# circuitdraft.net
KiCad netlist of a schematic drawn in EAGLE
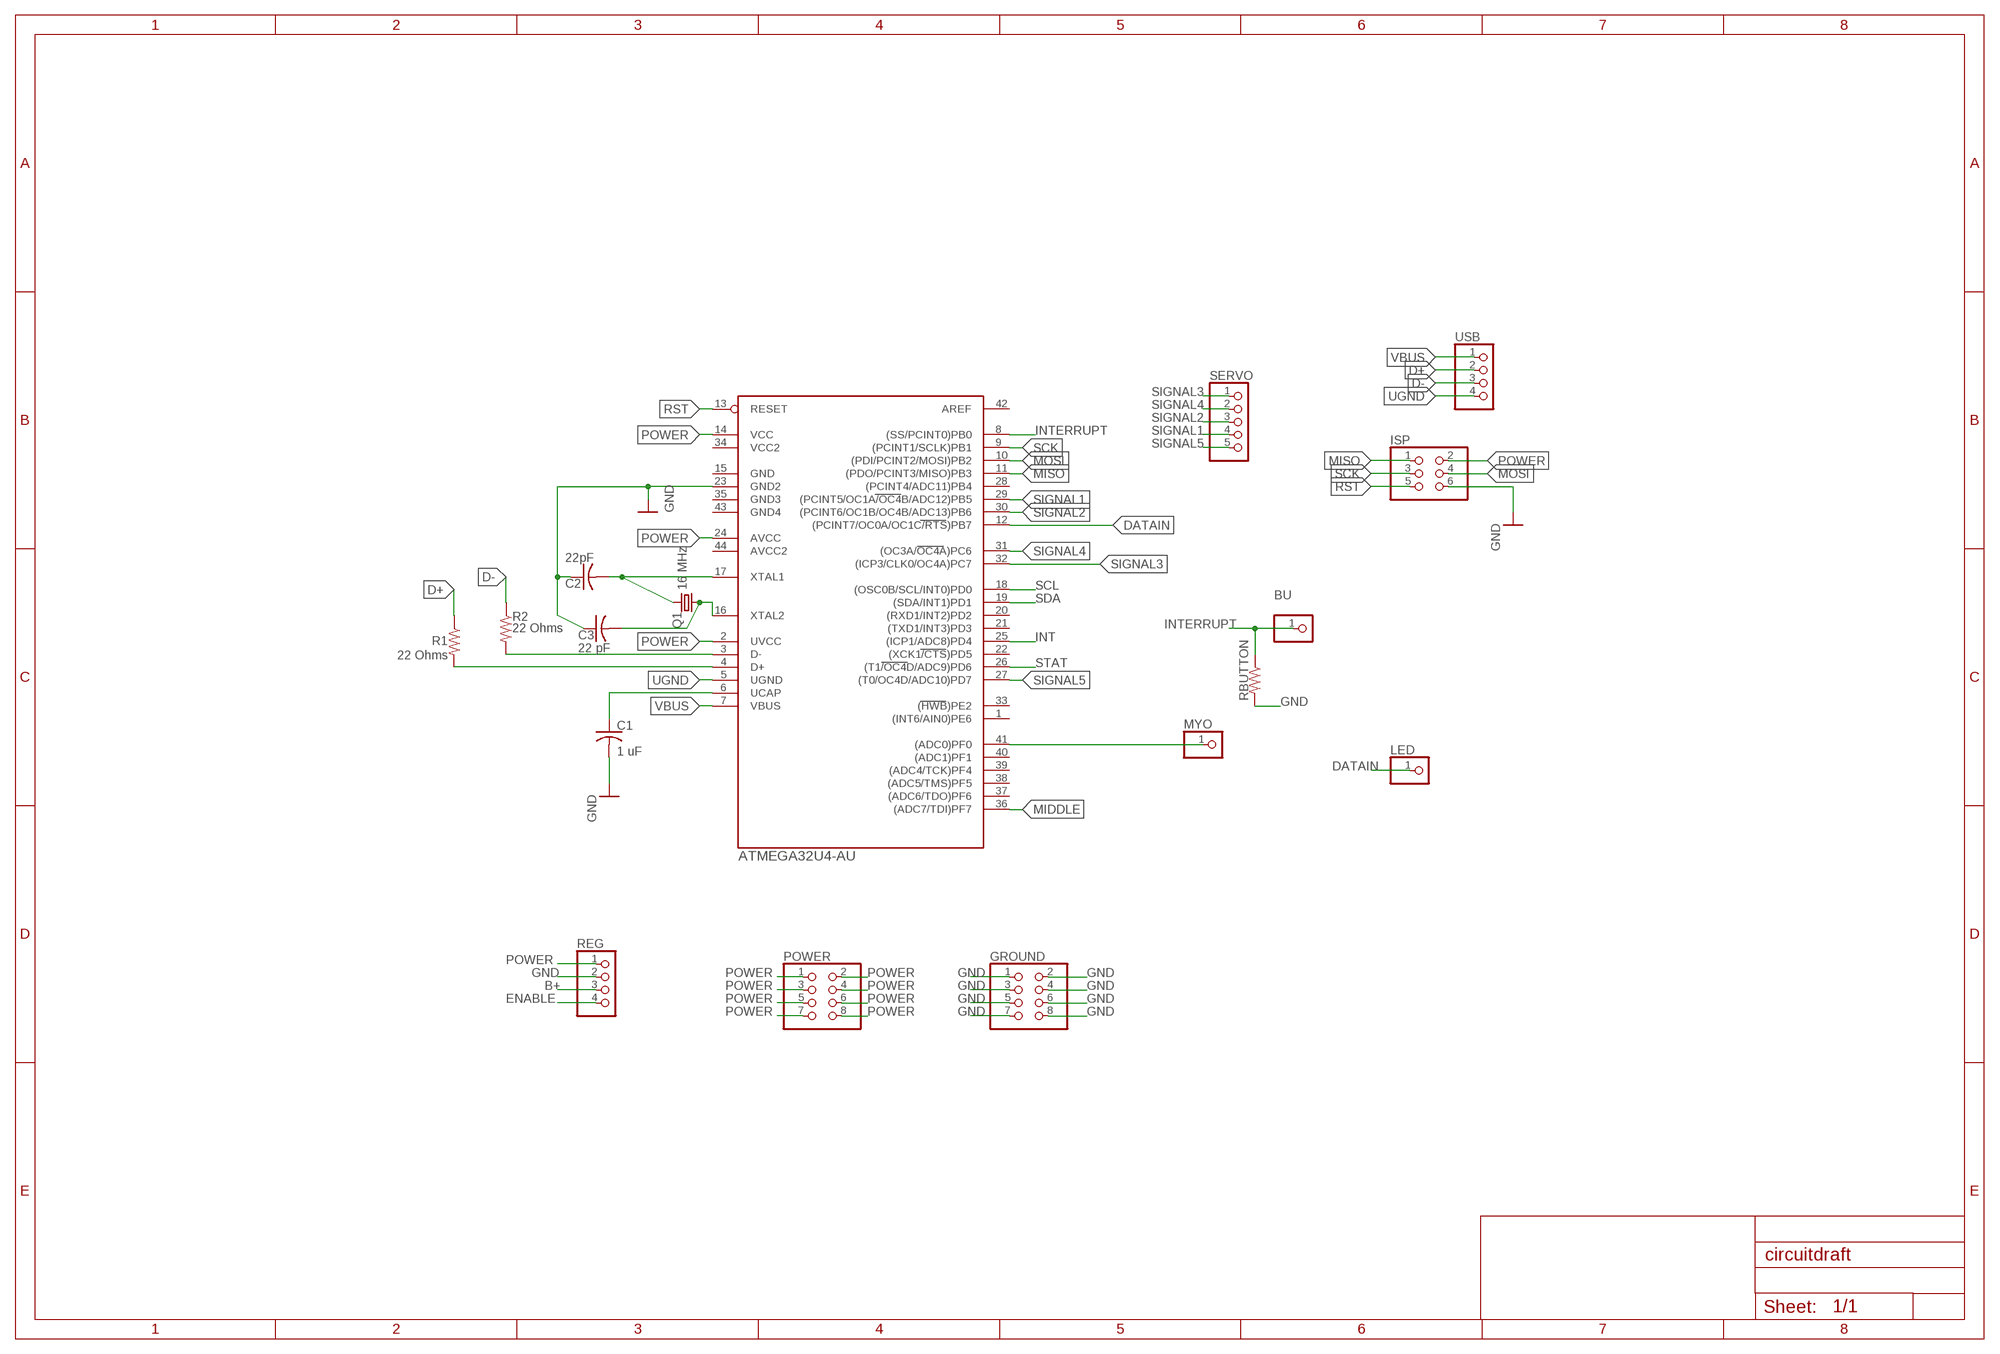
[diagram p0: schematic, sheet 1]

(export (version "E")
  (design (tool "Eeschema 10.0.6"))
  (components
    (comp (ref "BU")
      (value "PINHD-1X1")
      (footprint "eagle-import:1X01")
      (libsource (lib "eagle-import") (part "PINHD-1X1"))
    )
    (comp (ref "C1")
      (value "1 uF")
      (footprint "eagle-import:C0603")
      (libsource (lib "eagle-import") (part "C-USC0603"))
    )
    (comp (ref "C2")
      (value "22pF")
      (footprint "eagle-import:C0603")
      (libsource (lib "eagle-import") (part "C-USC0603"))
    )
    (comp (ref "C3")
      (value "22 pF")
      (footprint "eagle-import:C0603")
      (libsource (lib "eagle-import") (part "C-USC0603"))
    )
    (comp (ref "GROUND")
      (value "PINHD-2X4")
      (footprint "eagle-import:2X04")
      (libsource (lib "eagle-import") (part "PINHD-2X4"))
    )
    (comp (ref "ISP")
      (value "PINHD-2X3")
      (footprint "eagle-import:2X03")
      (libsource (lib "eagle-import") (part "PINHD-2X3"))
    )
    (comp (ref "LED")
      (value "PINHD-1X1")
      (footprint "eagle-import:1X01")
      (libsource (lib "eagle-import") (part "PINHD-1X1"))
    )
    (comp (ref "MYO")
      (value "PINHD-1X1")
      (footprint "eagle-import:1X01")
      (libsource (lib "eagle-import") (part "PINHD-1X1"))
    )
    (comp (ref "POWER")
      (value "PINHD-2X4")
      (footprint "eagle-import:2X04")
      (libsource (lib "eagle-import") (part "PINHD-2X4"))
    )
    (comp (ref "Q1")
      (value "16 MHz")
      (footprint "eagle-import:2.0X1.6_KX-5")
      (libsource (lib "eagle-import") (part "KX-5"))
    )
    (comp (ref "R1")
      (value "22 Ohms")
      (footprint "eagle-import:R0603")
      (libsource (lib "eagle-import") (part "R-US_R0603"))
    )
    (comp (ref "R2")
      (value "22 Ohms")
      (footprint "eagle-import:R0603")
      (libsource (lib "eagle-import") (part "R-US_R0603"))
    )
    (comp (ref "RBUTTON")
      (value "220 Ohm")
      (footprint "eagle-import:R0603")
      (libsource (lib "eagle-import") (part "R-US_R0603"))
    )
    (comp (ref "REG")
      (value "PINHD-1X4")
      (footprint "eagle-import:1X04")
      (libsource (lib "eagle-import") (part "PINHD-1X4"))
    )
    (comp (ref "SERVO")
      (value "PINHD-1X5")
      (footprint "eagle-import:1X05")
      (libsource (lib "eagle-import") (part "PINHD-1X5"))
    )
    (comp (ref "U$1")
      (value "ATMEGA32U4-AU")
      (footprint "eagle-import:TQFP44")
      (libsource (lib "eagle-import") (part "ATMEGA32U4-AU"))
    )
    (comp (ref "USB")
      (value "PINHD-1X4")
      (footprint "eagle-import:1X04")
      (libsource (lib "eagle-import") (part "PINHD-1X4"))
    )
  )
  (nets
    (net (code "1") (name "/B+") (class "Default")
      (node (ref "REG") (pin "3") (pinfunction "3_3") (pintype "passive"))
    )
    (net (code "2") (name "/ENABLE") (class "Default")
      (node (ref "REG") (pin "4") (pinfunction "4_4") (pintype "passive"))
    )
    (net (code "3") (name "/INT") (class "Default")
      (node (ref "U$1") (pin "25") (pinfunction "(ICP1/ADC8)PD4_25") (pintype "bidirectional"))
    )
    (net (code "4") (name "/INTERRUPT") (class "Default")
      (node (ref "BU") (pin "1") (pinfunction "1_1") (pintype "passive"))
      (node (ref "RBUTTON") (pin "1") (pinfunction "1_1") (pintype "passive"))
      (node (ref "U$1") (pin "8") (pinfunction "(SS/PCINT0)PB0_8") (pintype "bidirectional"))
    )
    (net (code "5") (name "/SCL") (class "Default")
      (node (ref "U$1") (pin "18") (pinfunction "(OSC0B/SCL/INT0)PD0_18") (pintype "bidirectional"))
    )
    (net (code "6") (name "/SDA") (class "Default")
      (node (ref "U$1") (pin "19") (pinfunction "(SDA/INT1)PD1_19") (pintype "bidirectional"))
    )
    (net (code "7") (name "/STAT") (class "Default")
      (node (ref "U$1") (pin "26") (pinfunction "(T1/OC4D/ADC9)PD6_26") (pintype "bidirectional"))
    )
    (net (code "8") (name "D+") (class "Default")
      (node (ref "R1") (pin "1") (pinfunction "1_1") (pintype "passive"))
      (node (ref "USB") (pin "2") (pinfunction "2_2") (pintype "passive"))
    )
    (net (code "9") (name "D-") (class "Default")
      (node (ref "R2") (pin "1") (pinfunction "1_1") (pintype "passive"))
      (node (ref "USB") (pin "3") (pinfunction "3_3") (pintype "passive"))
    )
    (net (code "10") (name "DATAIN") (class "Default")
      (node (ref "LED") (pin "1") (pinfunction "1_1") (pintype "passive"))
      (node (ref "U$1") (pin "12") (pinfunction "(PCINT7/OC0A/OC1C/RTS)PB7_12") (pintype "bidirectional"))
    )
    (net (code "11") (name "GND") (class "Default")
      (node (ref "C1") (pin "2") (pinfunction "2_2") (pintype "passive"))
      (node (ref "C2") (pin "1") (pinfunction "1_1") (pintype "passive"))
      (node (ref "C3") (pin "1") (pinfunction "1_1") (pintype "passive"))
      (node (ref "GROUND") (pin "1") (pinfunction "1_1") (pintype "passive"))
      (node (ref "GROUND") (pin "2") (pinfunction "2_2") (pintype "passive"))
      (node (ref "GROUND") (pin "3") (pinfunction "3_3") (pintype "passive"))
      (node (ref "GROUND") (pin "4") (pinfunction "4_4") (pintype "passive"))
      (node (ref "GROUND") (pin "5") (pinfunction "5_5") (pintype "passive"))
      (node (ref "GROUND") (pin "6") (pinfunction "6_6") (pintype "passive"))
      (node (ref "GROUND") (pin "7") (pinfunction "7_7") (pintype "passive"))
      (node (ref "GROUND") (pin "8") (pinfunction "8_8") (pintype "passive"))
      (node (ref "ISP") (pin "6") (pinfunction "6_6") (pintype "passive"))
      (node (ref "RBUTTON") (pin "2") (pinfunction "2_2") (pintype "passive"))
      (node (ref "REG") (pin "2") (pinfunction "2_2") (pintype "passive"))
      (node (ref "U$1") (pin "23") (pinfunction "GND2_23") (pintype "bidirectional"))
    )
    (net (code "12") (name "MIDDLE") (class "Default")
      (node (ref "U$1") (pin "36") (pinfunction "(ADC7/TDI)PF7_36") (pintype "bidirectional"))
    )
    (net (code "13") (name "MISO") (class "Default")
      (node (ref "ISP") (pin "1") (pinfunction "1_1") (pintype "passive"))
      (node (ref "U$1") (pin "11") (pinfunction "(PDO/PCINT3/MISO)PB3_11") (pintype "bidirectional"))
    )
    (net (code "14") (name "MOSI") (class "Default")
      (node (ref "ISP") (pin "4") (pinfunction "4_4") (pintype "passive"))
      (node (ref "U$1") (pin "10") (pinfunction "(PDI/PCINT2/MOSI)PB2_10") (pintype "bidirectional"))
    )
    (net (code "15") (name "Net-(Q1-2)") (class "Default")
      (node (ref "C2") (pin "2") (pinfunction "2_2") (pintype "passive"))
      (node (ref "Q1") (pin "3") (pinfunction "2_3") (pintype "passive"))
      (node (ref "U$1") (pin "17") (pinfunction "XTAL1_17") (pintype "bidirectional"))
    )
    (net (code "16") (name "Net-(U$1-(ADC0)PF0)") (class "Default")
      (node (ref "MYO") (pin "1") (pinfunction "1_1") (pintype "passive"))
      (node (ref "U$1") (pin "41") (pinfunction "(ADC0)PF0_41") (pintype "bidirectional"))
    )
    (net (code "17") (name "Net-(U$1-D+)") (class "Default")
      (node (ref "R1") (pin "2") (pinfunction "2_2") (pintype "passive"))
      (node (ref "U$1") (pin "4") (pinfunction "D+_4") (pintype "bidirectional"))
    )
    (net (code "18") (name "Net-(U$1-D-)") (class "Default")
      (node (ref "R2") (pin "2") (pinfunction "2_2") (pintype "passive"))
      (node (ref "U$1") (pin "3") (pinfunction "D-_3") (pintype "bidirectional"))
    )
    (net (code "19") (name "Net-(U$1-UCAP)") (class "Default")
      (node (ref "C1") (pin "1") (pinfunction "1_1") (pintype "passive"))
      (node (ref "U$1") (pin "6") (pinfunction "UCAP_6") (pintype "bidirectional"))
    )
    (net (code "20") (name "Net-(U$1-XTAL2)") (class "Default")
      (node (ref "C3") (pin "2") (pinfunction "2_2") (pintype "passive"))
      (node (ref "Q1") (pin "1") (pinfunction "1_1") (pintype "passive"))
      (node (ref "U$1") (pin "16") (pinfunction "XTAL2_16") (pintype "bidirectional"))
    )
    (net (code "21") (name "POWER") (class "Default")
      (node (ref "ISP") (pin "2") (pinfunction "2_2") (pintype "passive"))
      (node (ref "POWER") (pin "1") (pinfunction "1_1") (pintype "passive"))
      (node (ref "POWER") (pin "2") (pinfunction "2_2") (pintype "passive"))
      (node (ref "POWER") (pin "3") (pinfunction "3_3") (pintype "passive"))
      (node (ref "POWER") (pin "4") (pinfunction "4_4") (pintype "passive"))
      (node (ref "POWER") (pin "5") (pinfunction "5_5") (pintype "passive"))
      (node (ref "POWER") (pin "6") (pinfunction "6_6") (pintype "passive"))
      (node (ref "POWER") (pin "7") (pinfunction "7_7") (pintype "passive"))
      (node (ref "POWER") (pin "8") (pinfunction "8_8") (pintype "passive"))
      (node (ref "REG") (pin "1") (pinfunction "1_1") (pintype "passive"))
      (node (ref "U$1") (pin "14") (pinfunction "VCC_14") (pintype "bidirectional"))
      (node (ref "U$1") (pin "2") (pinfunction "UVCC_2") (pintype "bidirectional"))
      (node (ref "U$1") (pin "24") (pinfunction "AVCC_24") (pintype "bidirectional"))
    )
    (net (code "22") (name "RST") (class "Default")
      (node (ref "ISP") (pin "5") (pinfunction "5_5") (pintype "passive"))
      (node (ref "U$1") (pin "13") (pinfunction "RESET_13") (pintype "bidirectional"))
    )
    (net (code "23") (name "SCK") (class "Default")
      (node (ref "ISP") (pin "3") (pinfunction "3_3") (pintype "passive"))
      (node (ref "U$1") (pin "9") (pinfunction "(PCINT1/SCLK)PB1_9") (pintype "bidirectional"))
    )
    (net (code "24") (name "SIGNAL1") (class "Default")
      (node (ref "SERVO") (pin "4") (pinfunction "4_4") (pintype "passive"))
      (node (ref "U$1") (pin "29") (pinfunction "(PCINT5/OC1A/OC4B/ADC12)PB5_29") (pintype "bidirectional"))
    )
    (net (code "25") (name "SIGNAL2") (class "Default")
      (node (ref "SERVO") (pin "3") (pinfunction "3_3") (pintype "passive"))
      (node (ref "U$1") (pin "30") (pinfunction "(PCINT6/OC1B/OC4B/ADC13)PB6_30") (pintype "bidirectional"))
    )
    (net (code "26") (name "SIGNAL3") (class "Default")
      (node (ref "SERVO") (pin "1") (pinfunction "1_1") (pintype "passive"))
      (node (ref "U$1") (pin "32") (pinfunction "(ICP3/CLK0/OC4A)PC7_32") (pintype "bidirectional"))
    )
    (net (code "27") (name "SIGNAL4") (class "Default")
      (node (ref "SERVO") (pin "2") (pinfunction "2_2") (pintype "passive"))
      (node (ref "U$1") (pin "31") (pinfunction "(OC3A/OC4A)PC6_31") (pintype "bidirectional"))
    )
    (net (code "28") (name "SIGNAL5") (class "Default")
      (node (ref "SERVO") (pin "5") (pinfunction "5_5") (pintype "passive"))
      (node (ref "U$1") (pin "27") (pinfunction "(T0/OC4D/ADC10)PD7_27") (pintype "bidirectional"))
    )
    (net (code "29") (name "UGND") (class "Default")
      (node (ref "U$1") (pin "5") (pinfunction "UGND_5") (pintype "bidirectional"))
      (node (ref "USB") (pin "4") (pinfunction "4_4") (pintype "passive"))
    )
    (net (code "30") (name "VBUS") (class "Default")
      (node (ref "U$1") (pin "7") (pinfunction "VBUS_7") (pintype "bidirectional"))
      (node (ref "USB") (pin "1") (pinfunction "1_1") (pintype "passive"))
    )
    (net (code "31") (name "unconnected-(U$1-(ADC1)PF1-Pad40)") (class "Default")
      (node (ref "U$1") (pin "40") (pinfunction "(ADC1)PF1_40") (pintype "bidirectional"))
    )
    (net (code "32") (name "unconnected-(U$1-(ADC4{slash}TCK)PF4-Pad39)") (class "Default")
      (node (ref "U$1") (pin "39") (pinfunction "(ADC4/TCK)PF4_39") (pintype "bidirectional"))
    )
    (net (code "33") (name "unconnected-(U$1-(ADC5{slash}TMS)PF5-Pad38)") (class "Default")
      (node (ref "U$1") (pin "38") (pinfunction "(ADC5/TMS)PF5_38") (pintype "bidirectional"))
    )
    (net (code "34") (name "unconnected-(U$1-(ADC6{slash}TDO)PF6-Pad37)") (class "Default")
      (node (ref "U$1") (pin "37") (pinfunction "(ADC6/TDO)PF6_37") (pintype "bidirectional"))
    )
    (net (code "35") (name "unconnected-(U$1-(HWB)PE2-Pad33)") (class "Default")
      (node (ref "U$1") (pin "33") (pinfunction "(HWB)PE2_33") (pintype "bidirectional"))
    )
    (net (code "36") (name "unconnected-(U$1-(INT6{slash}AIN0)PE6-Pad1)") (class "Default")
      (node (ref "U$1") (pin "1") (pinfunction "(INT6/AIN0)PE6_1") (pintype "bidirectional"))
    )
    (net (code "37") (name "unconnected-(U$1-(PCINT4{slash}ADC11)PB4-Pad28)") (class "Default")
      (node (ref "U$1") (pin "28") (pinfunction "(PCINT4/ADC11)PB4_28") (pintype "bidirectional"))
    )
    (net (code "38") (name "unconnected-(U$1-(RXD1{slash}INT2)PD2-Pad20)") (class "Default")
      (node (ref "U$1") (pin "20") (pinfunction "(RXD1/INT2)PD2_20") (pintype "bidirectional"))
    )
    (net (code "39") (name "unconnected-(U$1-(TXD1{slash}INT3)PD3-Pad21)") (class "Default")
      (node (ref "U$1") (pin "21") (pinfunction "(TXD1/INT3)PD3_21") (pintype "bidirectional"))
    )
    (net (code "40") (name "unconnected-(U$1-(XCK1{slash}CTS)PD5-Pad22)") (class "Default")
      (node (ref "U$1") (pin "22") (pinfunction "(XCK1/CTS)PD5_22") (pintype "bidirectional"))
    )
    (net (code "41") (name "unconnected-(U$1-AREF-Pad42)") (class "Default")
      (node (ref "U$1") (pin "42") (pinfunction "AREF_42") (pintype "bidirectional"))
    )
    (net (code "42") (name "unconnected-(U$1-AVCC2-Pad44)") (class "Default")
      (node (ref "U$1") (pin "44") (pinfunction "AVCC2_44") (pintype "bidirectional"))
    )
    (net (code "43") (name "unconnected-(U$1-GND-Pad15)") (class "Default")
      (node (ref "U$1") (pin "15") (pinfunction "GND_15") (pintype "bidirectional"))
    )
    (net (code "44") (name "unconnected-(U$1-GND3-Pad35)") (class "Default")
      (node (ref "U$1") (pin "35") (pinfunction "GND3_35") (pintype "bidirectional"))
    )
    (net (code "45") (name "unconnected-(U$1-GND4-Pad43)") (class "Default")
      (node (ref "U$1") (pin "43") (pinfunction "GND4_43") (pintype "bidirectional"))
    )
    (net (code "46") (name "unconnected-(U$1-VCC2-Pad34)") (class "Default")
      (node (ref "U$1") (pin "34") (pinfunction "VCC2_34") (pintype "bidirectional"))
    )
  )
)
